# Motor_Controller.net
KiCad netlist of a schematic drawn in Altium Designer
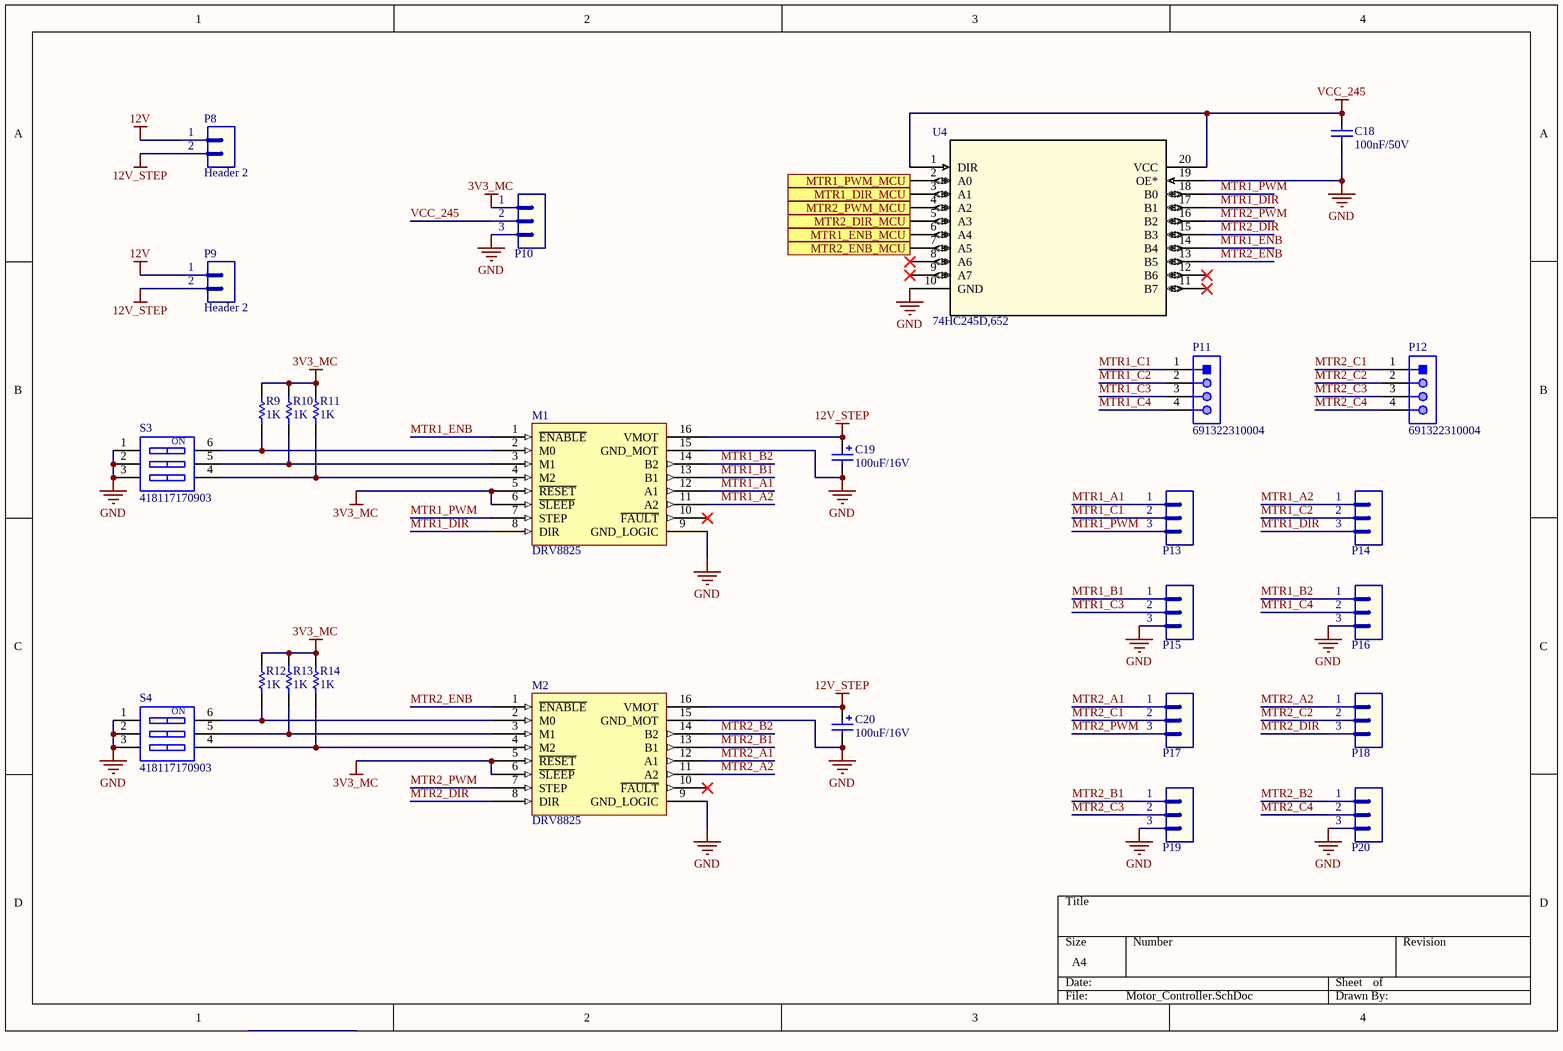
[diagram p0: Motor_Controller.SchDoc]

(export (version "E")
  (design (tool "Eeschema 10.0.6"))
  (components
    (comp (ref "C18")
      (value "100nF/50V")
      (footprint "CAP-SM-0805")
      (description "CAP CER 0.1UF 50V Y5V 0805")
      (fields
        (field (name "MANUFACTURER") "Samsung Electro-Mechanics")
        (field (name "MANUFACTURER PART NUMBER") "CL21F104ZBCNNNC")
      )
      (libsource (lib "Capacitor") (part "Cap-100nF-50V-0805"))
    )
    (comp (ref "C19")
      (value "100uF/16V")
      (footprint "CAP-SM-AL-SIZE-D-D6L6")
      (description "CAP ALUM 100UF 20% 16V SMD")
      (fields
        (field (name "MANUFACTURER") "Nichicon")
        (field (name "MANUFACTURER PART NUMBER") "UWX1C101MCL1GB")
      )
      (libsource (lib "Capacitor") (part "Cap-Al-100uF-16V-D6L5"))
    )
    (comp (ref "C20")
      (value "100uF/16V")
      (footprint "CAP-SM-AL-SIZE-D-D6L6")
      (description "CAP ALUM 100UF 20% 16V SMD")
      (fields
        (field (name "MANUFACTURER") "Nichicon")
        (field (name "MANUFACTURER PART NUMBER") "UWX1C101MCL1GB")
      )
      (libsource (lib "Capacitor") (part "Cap-Al-100uF-16V-D6L5"))
    )
    (comp (ref "M1")
      (value "DRV8825")
      (footprint "IC_DRV8825_STEPPER_MOTOR_DRIVER_CARRIER")
      (libsource (lib "Project_Xe_Can_Bang") (part "DRV8825"))
    )
    (comp (ref "M2")
      (value "DRV8825")
      (footprint "IC_DRV8825_STEPPER_MOTOR_DRIVER_CARRIER")
      (libsource (lib "Project_Xe_Can_Bang") (part "DRV8825"))
    )
    (comp (ref "P8")
      (value "Header 2")
      (footprint "Project_Xe_Can_Bang:JP2")
      (description "Header, 2-Pin")
      (fields (field (name "PUBLISHER") "Altium Limited"))
      (libsource (lib "Project_Xe_Can_Bang") (part "Header 2"))
    )
    (comp (ref "P9")
      (value "Header 2")
      (footprint "Project_Xe_Can_Bang:JP2")
      (description "Header, 2-Pin")
      (fields (field (name "PUBLISHER") "Altium Limited"))
      (libsource (lib "Project_Xe_Can_Bang") (part "Header 2"))
    )
    (comp (ref "P10")
      (value "Header 3")
      (footprint "Project_Xe_Can_Bang:JP3")
      (description "Header, 3-Pin")
      (fields (field (name "PUBLISHER") "Altium Limited"))
      (libsource (lib "Project_Xe_Can_Bang") (part "Header 3"))
    )
    (comp (ref "P11")
      (value "691322310004")
      (footprint "691322310004")
      (description "WR-TBL Serie 322 Horizontal PCB Header, Pluggable, pitch 3.81mm, 4p")
      (fields (field (name "PUBLISHER") "Wurth Elektronik"))
      (libsource (lib "Domino_691111710003_Altium_WR-TBL_rev19a") (part "691322310004"))
    )
    (comp (ref "P12")
      (value "691322310004")
      (footprint "691322310004")
      (description "WR-TBL Serie 322 Horizontal PCB Header, Pluggable, pitch 3.81mm, 4p")
      (fields (field (name "PUBLISHER") "Wurth Elektronik"))
      (libsource (lib "Domino_691111710003_Altium_WR-TBL_rev19a") (part "691322310004"))
    )
    (comp (ref "P13")
      (value "Header 3")
      (footprint "Project_Xe_Can_Bang:JP3")
      (description "Header, 3-Pin")
      (fields (field (name "PUBLISHER") "Altium Limited"))
      (libsource (lib "Project_Xe_Can_Bang") (part "Header 3"))
    )
    (comp (ref "P14")
      (value "Header 3")
      (footprint "Project_Xe_Can_Bang:JP3")
      (description "Header, 3-Pin")
      (fields (field (name "PUBLISHER") "Altium Limited"))
      (libsource (lib "Project_Xe_Can_Bang") (part "Header 3"))
    )
    (comp (ref "P15")
      (value "Header 3")
      (footprint "Project_Xe_Can_Bang:JP3")
      (description "Header, 3-Pin")
      (fields (field (name "PUBLISHER") "Altium Limited"))
      (libsource (lib "Project_Xe_Can_Bang") (part "Header 3"))
    )
    (comp (ref "P16")
      (value "Header 3")
      (footprint "Project_Xe_Can_Bang:JP3")
      (description "Header, 3-Pin")
      (fields (field (name "PUBLISHER") "Altium Limited"))
      (libsource (lib "Project_Xe_Can_Bang") (part "Header 3"))
    )
    (comp (ref "P17")
      (value "Header 3")
      (footprint "Project_Xe_Can_Bang:JP3")
      (description "Header, 3-Pin")
      (fields (field (name "PUBLISHER") "Altium Limited"))
      (libsource (lib "Project_Xe_Can_Bang") (part "Header 3"))
    )
    (comp (ref "P18")
      (value "Header 3")
      (footprint "Project_Xe_Can_Bang:JP3")
      (description "Header, 3-Pin")
      (fields (field (name "PUBLISHER") "Altium Limited"))
      (libsource (lib "Project_Xe_Can_Bang") (part "Header 3"))
    )
    (comp (ref "P19")
      (value "Header 3")
      (footprint "Project_Xe_Can_Bang:JP3")
      (description "Header, 3-Pin")
      (fields (field (name "PUBLISHER") "Altium Limited"))
      (libsource (lib "Project_Xe_Can_Bang") (part "Header 3"))
    )
    (comp (ref "P20")
      (value "Header 3")
      (footprint "Project_Xe_Can_Bang:JP3")
      (description "Header, 3-Pin")
      (fields (field (name "PUBLISHER") "Altium Limited"))
      (libsource (lib "Project_Xe_Can_Bang") (part "Header 3"))
    )
    (comp (ref "R9")
      (value "1K")
      (footprint "Resistor:RES-SM-0805")
      (description "RES 1K OHM 1% 1/4W 0805")
      (fields
        (field (name "MANUFACTURER") "Stackpole Electronics Inc")
        (field (name "MANUFACTURER PART NUMBER") "RNCP0805FTD1K00")
      )
      (libsource (lib "Resistor") (part "Res-1K-0805"))
    )
    (comp (ref "R10")
      (value "1K")
      (footprint "Resistor:RES-SM-0805")
      (description "RES 1K OHM 1% 1/4W 0805")
      (fields
        (field (name "MANUFACTURER") "Stackpole Electronics Inc")
        (field (name "MANUFACTURER PART NUMBER") "RNCP0805FTD1K00")
      )
      (libsource (lib "Resistor") (part "Res-1K-0805"))
    )
    (comp (ref "R11")
      (value "1K")
      (footprint "Resistor:RES-SM-0805")
      (description "RES 1K OHM 1% 1/4W 0805")
      (fields
        (field (name "MANUFACTURER") "Stackpole Electronics Inc")
        (field (name "MANUFACTURER PART NUMBER") "RNCP0805FTD1K00")
      )
      (libsource (lib "Resistor") (part "Res-1K-0805"))
    )
    (comp (ref "R12")
      (value "1K")
      (footprint "Resistor:RES-SM-0805")
      (description "RES 1K OHM 1% 1/4W 0805")
      (fields
        (field (name "MANUFACTURER") "Stackpole Electronics Inc")
        (field (name "MANUFACTURER PART NUMBER") "RNCP0805FTD1K00")
      )
      (libsource (lib "Resistor") (part "Res-1K-0805"))
    )
    (comp (ref "R13")
      (value "1K")
      (footprint "Resistor:RES-SM-0805")
      (description "RES 1K OHM 1% 1/4W 0805")
      (fields
        (field (name "MANUFACTURER") "Stackpole Electronics Inc")
        (field (name "MANUFACTURER PART NUMBER") "RNCP0805FTD1K00")
      )
      (libsource (lib "Resistor") (part "Res-1K-0805"))
    )
    (comp (ref "R14")
      (value "1K")
      (footprint "Resistor:RES-SM-0805")
      (description "RES 1K OHM 1% 1/4W 0805")
      (fields
        (field (name "MANUFACTURER") "Stackpole Electronics Inc")
        (field (name "MANUFACTURER PART NUMBER") "RNCP0805FTD1K00")
      )
      (libsource (lib "Resistor") (part "Res-1K-0805"))
    )
    (comp (ref "S3")
      (value "418117170903")
      (footprint "Project_Xe_Can_Bang:418117170903")
      (description "WS-DITV Compact THT Dip Switch, Flat Actuator, pitch 2.54mm, 3p")
      (fields (field (name "PUBLISHER") "Wurth Elektronik"))
      (libsource (lib "Project_Xe_Can_Bang") (part "418117170903"))
    )
    (comp (ref "S4")
      (value "418117170903")
      (footprint "Project_Xe_Can_Bang:418117170903")
      (description "WS-DITV Compact THT Dip Switch, Flat Actuator, pitch 2.54mm, 3p")
      (fields (field (name "PUBLISHER") "Wurth Elektronik"))
      (libsource (lib "Project_Xe_Can_Bang") (part "418117170903"))
    )
    (comp (ref "U4")
      (value "74HC245D,652")
      (footprint "SOT163-1_NEX")
      (description "No Description Available")
      (fields (field (name "COPYRIGHT") "Copyright (C) 2016 Accelerated Designs. All rights reserved"))
      (libsource (lib "74HC245D_652_2020-06-19_16-38-41") (part "74HC245D,652"))
    )
  )
  (nets
    (net (code "1") (name "/MTR1_A1") (class "Default")
      (node (ref "M1") (pin "12") (pinfunction "A1_12") (pintype "output"))
      (node (ref "P13") (pin "1") (pinfunction "1_1") (pintype "passive"))
    )
    (net (code "2") (name "/MTR1_A2") (class "Default")
      (node (ref "M1") (pin "11") (pinfunction "A2_11") (pintype "output"))
      (node (ref "P14") (pin "1") (pinfunction "1_1") (pintype "passive"))
    )
    (net (code "3") (name "/MTR1_B1") (class "Default")
      (node (ref "M1") (pin "13") (pinfunction "B1_13") (pintype "output"))
      (node (ref "P15") (pin "1") (pinfunction "1_1") (pintype "passive"))
    )
    (net (code "4") (name "/MTR1_B2") (class "Default")
      (node (ref "M1") (pin "14") (pinfunction "B2_14") (pintype "output"))
      (node (ref "P16") (pin "1") (pinfunction "1_1") (pintype "passive"))
    )
    (net (code "5") (name "/MTR1_C1") (class "Default")
      (node (ref "P11") (pin "1") (pinfunction "1_1") (pintype "passive"))
      (node (ref "P13") (pin "2") (pinfunction "2_2") (pintype "passive"))
    )
    (net (code "6") (name "/MTR1_C2") (class "Default")
      (node (ref "P11") (pin "2") (pinfunction "2_2") (pintype "passive"))
      (node (ref "P14") (pin "2") (pinfunction "2_2") (pintype "passive"))
    )
    (net (code "7") (name "/MTR1_C3") (class "Default")
      (node (ref "P11") (pin "3") (pinfunction "3_3") (pintype "passive"))
      (node (ref "P15") (pin "2") (pinfunction "2_2") (pintype "passive"))
    )
    (net (code "8") (name "/MTR1_C4") (class "Default")
      (node (ref "P11") (pin "4") (pinfunction "4_4") (pintype "passive"))
      (node (ref "P16") (pin "2") (pinfunction "2_2") (pintype "passive"))
    )
    (net (code "9") (name "/MTR1_DIR") (class "Default")
      (node (ref "M1") (pin "8") (pinfunction "DIR_8") (pintype "input"))
      (node (ref "P14") (pin "3") (pinfunction "3_3") (pintype "passive"))
      (node (ref "U4") (pin "17") (pinfunction "B1_17") (pintype "bidirectional"))
    )
    (net (code "10") (name "/MTR1_DIR_MCU") (class "Default")
      (node (ref "U4") (pin "3") (pinfunction "A1_3") (pintype "bidirectional"))
    )
    (net (code "11") (name "/MTR1_ENB") (class "Default")
      (node (ref "M1") (pin "1") (pinfunction "~{ENABLE}_1") (pintype "input"))
      (node (ref "U4") (pin "14") (pinfunction "B4_14") (pintype "bidirectional"))
    )
    (net (code "12") (name "/MTR1_ENB_MCU") (class "Default")
      (node (ref "U4") (pin "6") (pinfunction "A4_6") (pintype "bidirectional"))
    )
    (net (code "13") (name "/MTR1_PWM") (class "Default")
      (node (ref "M1") (pin "7") (pinfunction "STEP_7") (pintype "input"))
      (node (ref "P13") (pin "3") (pinfunction "3_3") (pintype "passive"))
      (node (ref "U4") (pin "18") (pinfunction "B0_18") (pintype "bidirectional"))
    )
    (net (code "14") (name "/MTR1_PWM_MCU") (class "Default")
      (node (ref "U4") (pin "2") (pinfunction "A0_2") (pintype "bidirectional"))
    )
    (net (code "15") (name "/MTR2_A1") (class "Default")
      (node (ref "M2") (pin "12") (pinfunction "A1_12") (pintype "output"))
      (node (ref "P17") (pin "1") (pinfunction "1_1") (pintype "passive"))
    )
    (net (code "16") (name "/MTR2_A2") (class "Default")
      (node (ref "M2") (pin "11") (pinfunction "A2_11") (pintype "output"))
      (node (ref "P18") (pin "1") (pinfunction "1_1") (pintype "passive"))
    )
    (net (code "17") (name "/MTR2_B1") (class "Default")
      (node (ref "M2") (pin "13") (pinfunction "B1_13") (pintype "output"))
      (node (ref "P19") (pin "1") (pinfunction "1_1") (pintype "passive"))
    )
    (net (code "18") (name "/MTR2_B2") (class "Default")
      (node (ref "M2") (pin "14") (pinfunction "B2_14") (pintype "output"))
      (node (ref "P20") (pin "1") (pinfunction "1_1") (pintype "passive"))
    )
    (net (code "19") (name "/MTR2_C1") (class "Default")
      (node (ref "P12") (pin "1") (pinfunction "1_1") (pintype "passive"))
      (node (ref "P17") (pin "2") (pinfunction "2_2") (pintype "passive"))
    )
    (net (code "20") (name "/MTR2_C2") (class "Default")
      (node (ref "P12") (pin "2") (pinfunction "2_2") (pintype "passive"))
      (node (ref "P18") (pin "2") (pinfunction "2_2") (pintype "passive"))
    )
    (net (code "21") (name "/MTR2_C3") (class "Default")
      (node (ref "P12") (pin "3") (pinfunction "3_3") (pintype "passive"))
      (node (ref "P19") (pin "2") (pinfunction "2_2") (pintype "passive"))
    )
    (net (code "22") (name "/MTR2_C4") (class "Default")
      (node (ref "P12") (pin "4") (pinfunction "4_4") (pintype "passive"))
      (node (ref "P20") (pin "2") (pinfunction "2_2") (pintype "passive"))
    )
    (net (code "23") (name "/MTR2_DIR") (class "Default")
      (node (ref "M2") (pin "8") (pinfunction "DIR_8") (pintype "input"))
      (node (ref "P18") (pin "3") (pinfunction "3_3") (pintype "passive"))
      (node (ref "U4") (pin "15") (pinfunction "B3_15") (pintype "bidirectional"))
    )
    (net (code "24") (name "/MTR2_DIR_MCU") (class "Default")
      (node (ref "U4") (pin "5") (pinfunction "A3_5") (pintype "bidirectional"))
    )
    (net (code "25") (name "/MTR2_ENB") (class "Default")
      (node (ref "M2") (pin "1") (pinfunction "~{ENABLE}_1") (pintype "input"))
      (node (ref "U4") (pin "13") (pinfunction "B5_13") (pintype "bidirectional"))
    )
    (net (code "26") (name "/MTR2_ENB_MCU") (class "Default")
      (node (ref "U4") (pin "7") (pinfunction "A5_7") (pintype "bidirectional"))
    )
    (net (code "27") (name "/MTR2_PWM") (class "Default")
      (node (ref "M2") (pin "7") (pinfunction "STEP_7") (pintype "input"))
      (node (ref "P17") (pin "3") (pinfunction "3_3") (pintype "passive"))
      (node (ref "U4") (pin "16") (pinfunction "B2_16") (pintype "bidirectional"))
    )
    (net (code "28") (name "/MTR2_PWM_MCU") (class "Default")
      (node (ref "U4") (pin "4") (pinfunction "A2_4") (pintype "bidirectional"))
    )
    (net (code "29") (name "3V3_MC") (class "Default")
      (node (ref "M1") (pin "5") (pinfunction "~{RESET}_5") (pintype "input"))
      (node (ref "M1") (pin "6") (pinfunction "~{SLEEP}_6") (pintype "input"))
      (node (ref "M2") (pin "5") (pinfunction "~{RESET}_5") (pintype "input"))
      (node (ref "M2") (pin "6") (pinfunction "~{SLEEP}_6") (pintype "input"))
      (node (ref "P10") (pin "1") (pinfunction "1_1") (pintype "passive"))
      (node (ref "R10") (pin "1") (pinfunction "1_1") (pintype "passive"))
      (node (ref "R11") (pin "1") (pinfunction "1_1") (pintype "passive"))
      (node (ref "R12") (pin "1") (pinfunction "1_1") (pintype "passive"))
      (node (ref "R13") (pin "1") (pinfunction "1_1") (pintype "passive"))
      (node (ref "R14") (pin "1") (pinfunction "1_1") (pintype "passive"))
      (node (ref "R9") (pin "1") (pinfunction "1_1") (pintype "passive"))
    )
    (net (code "30") (name "12V") (class "Default")
      (node (ref "P8") (pin "1") (pinfunction "1_1") (pintype "passive"))
      (node (ref "P9") (pin "1") (pinfunction "1_1") (pintype "passive"))
    )
    (net (code "31") (name "12V_STEP") (class "Default")
      (node (ref "C19") (pin "1") (pinfunction "1_1") (pintype "passive"))
      (node (ref "C20") (pin "1") (pinfunction "1_1") (pintype "passive"))
      (node (ref "M1") (pin "16") (pinfunction "VMOT_16") (pintype "power_in"))
      (node (ref "M2") (pin "16") (pinfunction "VMOT_16") (pintype "power_in"))
      (node (ref "P8") (pin "2") (pinfunction "2_2") (pintype "passive"))
      (node (ref "P9") (pin "2") (pinfunction "2_2") (pintype "passive"))
    )
    (net (code "32") (name "GND") (class "Default")
      (node (ref "C18") (pin "1") (pinfunction "1_1") (pintype "passive"))
      (node (ref "C19") (pin "2") (pinfunction "2_2") (pintype "passive"))
      (node (ref "C20") (pin "2") (pinfunction "2_2") (pintype "passive"))
      (node (ref "M1") (pin "15") (pinfunction "GND_MOT_15") (pintype "passive"))
      (node (ref "M1") (pin "9") (pinfunction "GND_LOGIC_9") (pintype "passive"))
      (node (ref "M2") (pin "15") (pinfunction "GND_MOT_15") (pintype "passive"))
      (node (ref "M2") (pin "9") (pinfunction "GND_LOGIC_9") (pintype "passive"))
      (node (ref "P10") (pin "3") (pinfunction "3_3") (pintype "passive"))
      (node (ref "P15") (pin "3") (pinfunction "3_3") (pintype "passive"))
      (node (ref "P16") (pin "3") (pinfunction "3_3") (pintype "passive"))
      (node (ref "P19") (pin "3") (pinfunction "3_3") (pintype "passive"))
      (node (ref "P20") (pin "3") (pinfunction "3_3") (pintype "passive"))
      (node (ref "S3") (pin "1") (pinfunction "1_1") (pintype "passive"))
      (node (ref "S3") (pin "2") (pinfunction "2_2") (pintype "passive"))
      (node (ref "S3") (pin "3") (pinfunction "3_3") (pintype "passive"))
      (node (ref "S4") (pin "1") (pinfunction "1_1") (pintype "passive"))
      (node (ref "S4") (pin "2") (pinfunction "2_2") (pintype "passive"))
      (node (ref "S4") (pin "3") (pinfunction "3_3") (pintype "passive"))
      (node (ref "U4") (pin "10") (pinfunction "GND_10") (pintype "power_in"))
      (node (ref "U4") (pin "19") (pinfunction "OE*_19") (pintype "input"))
    )
    (net (code "33") (name "Net-(M1-M0)") (class "Default")
      (node (ref "M1") (pin "2") (pinfunction "M0_2") (pintype "input"))
      (node (ref "R9") (pin "2") (pinfunction "2_2") (pintype "passive"))
      (node (ref "S3") (pin "6") (pinfunction "6_6") (pintype "passive"))
    )
    (net (code "34") (name "Net-(M1-M1)") (class "Default")
      (node (ref "M1") (pin "3") (pinfunction "M1_3") (pintype "input"))
      (node (ref "R10") (pin "2") (pinfunction "2_2") (pintype "passive"))
      (node (ref "S3") (pin "5") (pinfunction "5_5") (pintype "passive"))
    )
    (net (code "35") (name "Net-(M1-M2)") (class "Default")
      (node (ref "M1") (pin "4") (pinfunction "M2_4") (pintype "input"))
      (node (ref "R11") (pin "2") (pinfunction "2_2") (pintype "passive"))
      (node (ref "S3") (pin "4") (pinfunction "4_4") (pintype "passive"))
    )
    (net (code "36") (name "Net-(M2-M0)") (class "Default")
      (node (ref "M2") (pin "2") (pinfunction "M0_2") (pintype "input"))
      (node (ref "R12") (pin "2") (pinfunction "2_2") (pintype "passive"))
      (node (ref "S4") (pin "6") (pinfunction "6_6") (pintype "passive"))
    )
    (net (code "37") (name "Net-(M2-M1)") (class "Default")
      (node (ref "M2") (pin "3") (pinfunction "M1_3") (pintype "input"))
      (node (ref "R13") (pin "2") (pinfunction "2_2") (pintype "passive"))
      (node (ref "S4") (pin "5") (pinfunction "5_5") (pintype "passive"))
    )
    (net (code "38") (name "Net-(M2-M2)") (class "Default")
      (node (ref "M2") (pin "4") (pinfunction "M2_4") (pintype "input"))
      (node (ref "R14") (pin "2") (pinfunction "2_2") (pintype "passive"))
      (node (ref "S4") (pin "4") (pinfunction "4_4") (pintype "passive"))
    )
    (net (code "39") (name "VCC_245") (class "Default")
      (node (ref "C18") (pin "2") (pinfunction "2_2") (pintype "passive"))
      (node (ref "P10") (pin "2") (pinfunction "2_2") (pintype "passive"))
      (node (ref "U4") (pin "1") (pinfunction "DIR_1") (pintype "input"))
      (node (ref "U4") (pin "20") (pinfunction "VCC_20") (pintype "power_in"))
    )
    (net (code "40") (name "unconnected-(M1-~{FAULT}-Pad10)") (class "Default")
      (node (ref "M1") (pin "10") (pinfunction "~{FAULT}_10") (pintype "output+no_connect"))
    )
    (net (code "41") (name "unconnected-(M2-~{FAULT}-Pad10)") (class "Default")
      (node (ref "M2") (pin "10") (pinfunction "~{FAULT}_10") (pintype "output+no_connect"))
    )
    (net (code "42") (name "unconnected-(U4-A6-Pad8)") (class "Default")
      (node (ref "U4") (pin "8") (pinfunction "A6_8") (pintype "bidirectional+no_connect"))
    )
    (net (code "43") (name "unconnected-(U4-A7-Pad9)") (class "Default")
      (node (ref "U4") (pin "9") (pinfunction "A7_9") (pintype "bidirectional+no_connect"))
    )
    (net (code "44") (name "unconnected-(U4-B6-Pad12)") (class "Default")
      (node (ref "U4") (pin "12") (pinfunction "B6_12") (pintype "bidirectional+no_connect"))
    )
    (net (code "45") (name "unconnected-(U4-B7-Pad11)") (class "Default")
      (node (ref "U4") (pin "11") (pinfunction "B7_11") (pintype "bidirectional+no_connect"))
    )
  )
)
